# megamidi.net
KiCad netlist of a schematic drawn in EAGLE
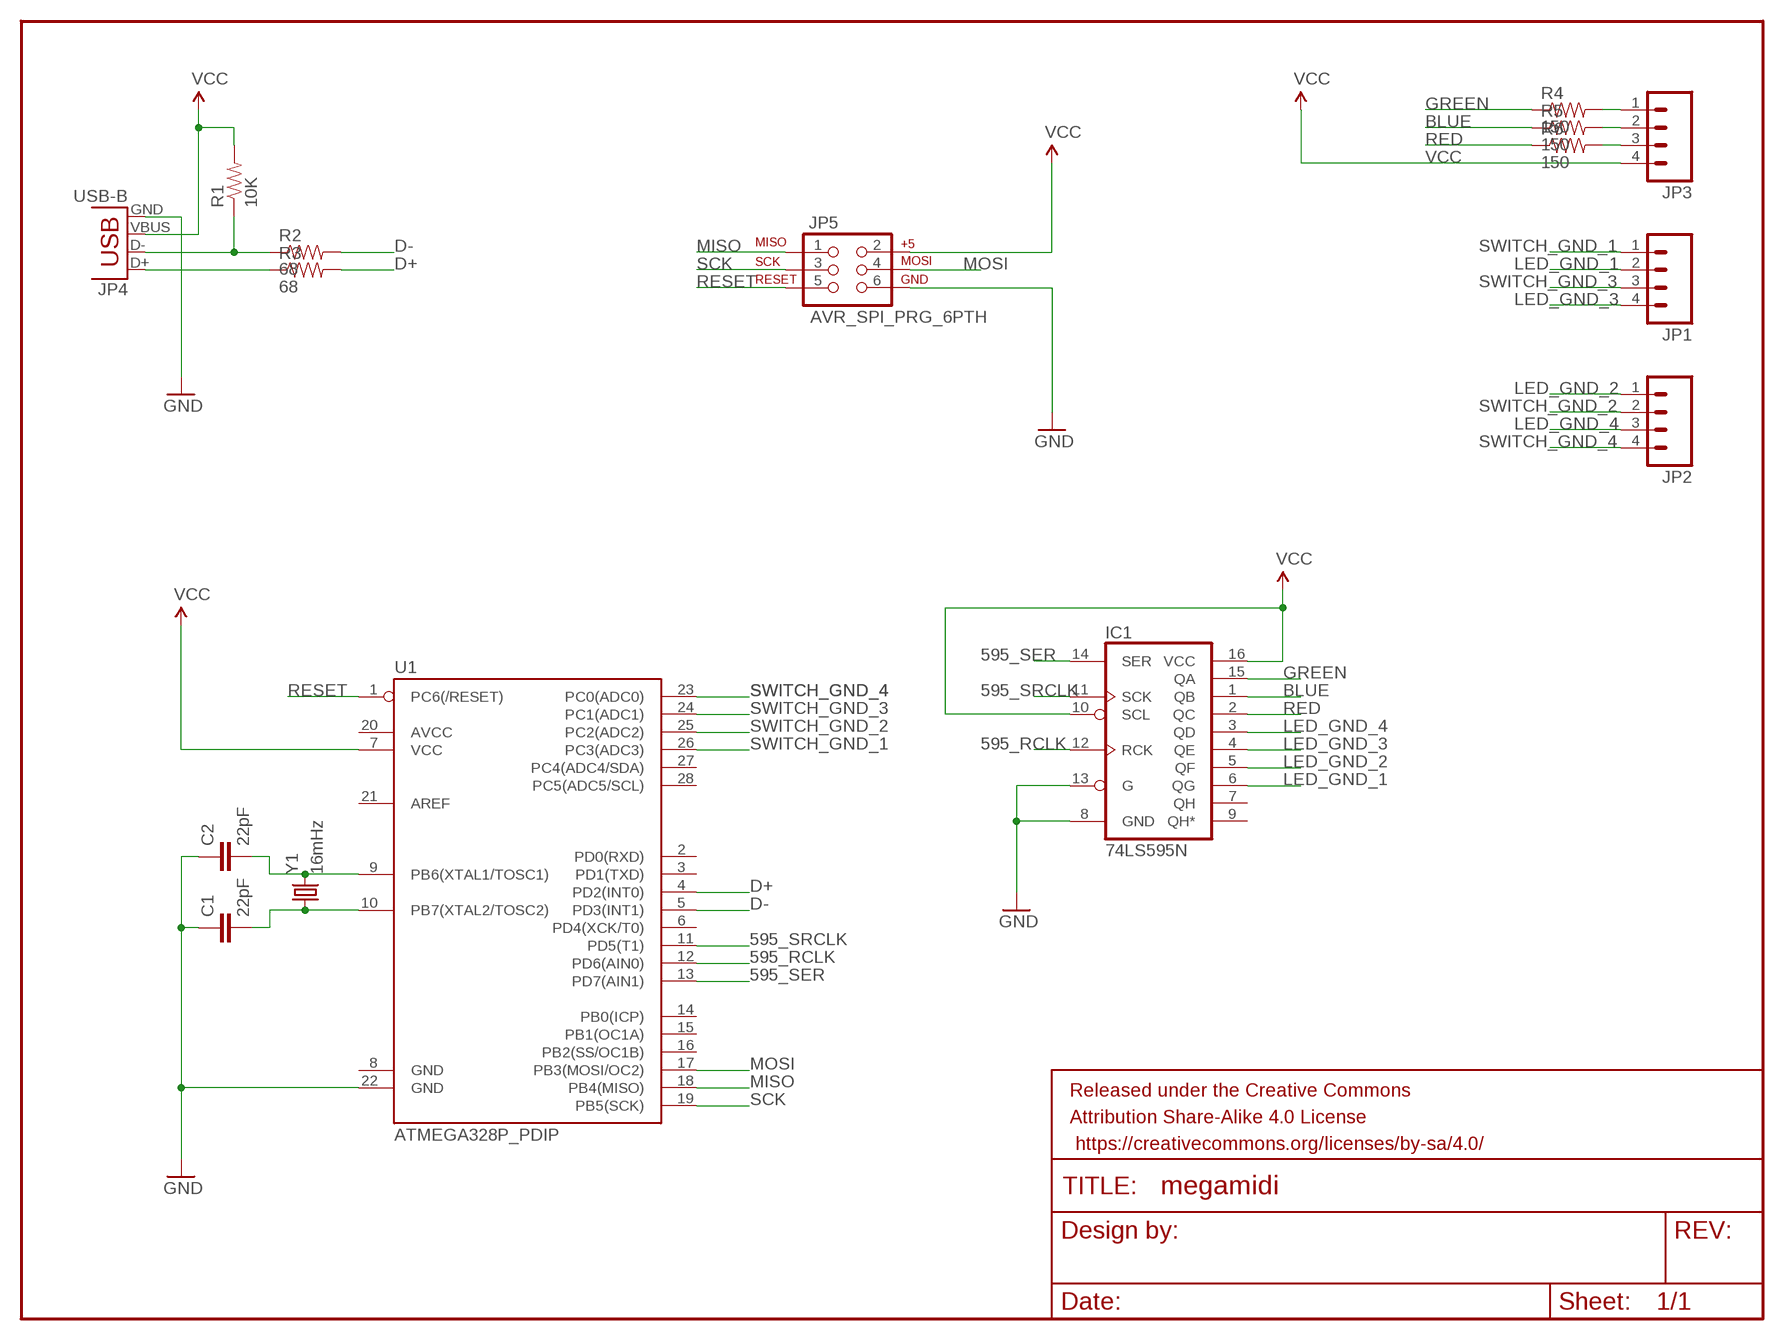
[diagram p0: schematic, sheet 1]

(export (version "E")
  (design (tool "Eeschema 10.0.6"))
  (components
    (comp (ref "C1")
      (value "22pF")
      (footprint "eagle-import:CAP-PTH-SMALL")
      (libsource (lib "eagle-import") (part "CAPPTH"))
    )
    (comp (ref "C2")
      (value "22pF")
      (footprint "eagle-import:CAP-PTH-SMALL")
      (libsource (lib "eagle-import") (part "CAPPTH"))
    )
    (comp (ref "FRAME1")
      (value "FRAME-LETTER")
      (footprint "eagle-import:CREATIVE_COMMONS")
      (libsource (lib "eagle-import") (part "FRAME-LETTER"))
    )
    (comp (ref "IC1")
      (value "74LS595N")
      (footprint "eagle-import:DIL16")
      (libsource (lib "eagle-import") (part "74595NLS"))
    )
    (comp (ref "JP1")
      (value "M04PTH")
      (footprint "eagle-import:1X04")
      (libsource (lib "eagle-import") (part "M04PTH"))
    )
    (comp (ref "JP2")
      (value "M04PTH")
      (footprint "eagle-import:1X04")
      (libsource (lib "eagle-import") (part "M04PTH"))
    )
    (comp (ref "JP3")
      (value "M04PTH")
      (footprint "eagle-import:1X04")
      (libsource (lib "eagle-import") (part "M04PTH"))
    )
    (comp (ref "JP4")
      (value "USB-B")
      (footprint "eagle-import:USB-B-PTH")
      (libsource (lib "eagle-import") (part "USBPTH"))
    )
    (comp (ref "JP5")
      (value "AVR_SPI_PRG_6PTH")
      (footprint "eagle-import:2X3")
      (libsource (lib "eagle-import") (part "AVR_SPI_PRG_6PTH"))
    )
    (comp (ref "R1")
      (value "10K")
      (footprint "eagle-import:AXIAL-0.1")
      (libsource (lib "eagle-import") (part "RESISTORPTH-1/4W-VERT"))
    )
    (comp (ref "R2")
      (value "68")
      (footprint "eagle-import:AXIAL-0.1")
      (libsource (lib "eagle-import") (part "RESISTORPTH-1/4W-VERT"))
    )
    (comp (ref "R3")
      (value "68")
      (footprint "eagle-import:AXIAL-0.1")
      (libsource (lib "eagle-import") (part "RESISTORPTH-1/4W-VERT"))
    )
    (comp (ref "R4")
      (value "150")
      (footprint "eagle-import:AXIAL-0.1")
      (libsource (lib "eagle-import") (part "RESISTORPTH-1/4W-VERT"))
    )
    (comp (ref "R5")
      (value "150")
      (footprint "eagle-import:AXIAL-0.1")
      (libsource (lib "eagle-import") (part "RESISTORPTH-1/4W-VERT"))
    )
    (comp (ref "R6")
      (value "150")
      (footprint "eagle-import:AXIAL-0.1")
      (libsource (lib "eagle-import") (part "RESISTORPTH-1/4W-VERT"))
    )
    (comp (ref "U1")
      (value "ATMEGA328P_PDIP")
      (footprint "eagle-import:DIL28-3")
      (libsource (lib "eagle-import") (part "ATMEGA328P_PDIP"))
    )
    (comp (ref "Y1")
      (value "16mHz")
      (footprint "eagle-import:HC49US")
      (libsource (lib "eagle-import") (part "CRYSTALHC49US"))
    )
  )
  (nets
    (net (code "1") (name "/595_RCLK") (class "Default")
      (node (ref "IC1") (pin "12") (pinfunction "RCK_12") (pintype "input"))
      (node (ref "U1") (pin "12") (pinfunction "PD6(AIN0)_12") (pintype "bidirectional"))
    )
    (net (code "2") (name "/595_SER") (class "Default")
      (node (ref "IC1") (pin "14") (pinfunction "SER_14") (pintype "input"))
      (node (ref "U1") (pin "13") (pinfunction "PD7(AIN1)_13") (pintype "bidirectional"))
    )
    (net (code "3") (name "/595_SRCLK") (class "Default")
      (node (ref "IC1") (pin "11") (pinfunction "SCK_11") (pintype "input"))
      (node (ref "U1") (pin "11") (pinfunction "PD5(T1)_11") (pintype "bidirectional"))
    )
    (net (code "4") (name "/BLUE") (class "Default")
      (node (ref "IC1") (pin "1") (pinfunction "QB_1") (pintype "tri_state"))
      (node (ref "R5") (pin "P$1") (pinfunction "1_P$1") (pintype "passive"))
    )
    (net (code "5") (name "/D+") (class "Default")
      (node (ref "R3") (pin "P$2") (pinfunction "2_P$2") (pintype "passive"))
      (node (ref "U1") (pin "4") (pinfunction "PD2(INT0)_4") (pintype "bidirectional"))
    )
    (net (code "6") (name "/D-") (class "Default")
      (node (ref "R2") (pin "P$2") (pinfunction "2_P$2") (pintype "passive"))
      (node (ref "U1") (pin "5") (pinfunction "PD3(INT1)_5") (pintype "bidirectional"))
    )
    (net (code "7") (name "/GREEN") (class "Default")
      (node (ref "IC1") (pin "15") (pinfunction "QA_15") (pintype "tri_state"))
      (node (ref "R4") (pin "P$1") (pinfunction "1_P$1") (pintype "passive"))
    )
    (net (code "8") (name "/LED_GND_1") (class "Default")
      (node (ref "IC1") (pin "6") (pinfunction "QG_6") (pintype "tri_state"))
      (node (ref "JP1") (pin "2") (pinfunction "2_2") (pintype "passive"))
    )
    (net (code "9") (name "/LED_GND_2") (class "Default")
      (node (ref "IC1") (pin "5") (pinfunction "QF_5") (pintype "tri_state"))
      (node (ref "JP2") (pin "1") (pinfunction "1_1") (pintype "passive"))
    )
    (net (code "10") (name "/LED_GND_3") (class "Default")
      (node (ref "IC1") (pin "4") (pinfunction "QE_4") (pintype "tri_state"))
      (node (ref "JP1") (pin "4") (pinfunction "4_4") (pintype "passive"))
    )
    (net (code "11") (name "/LED_GND_4") (class "Default")
      (node (ref "IC1") (pin "3") (pinfunction "QD_3") (pintype "tri_state"))
      (node (ref "JP2") (pin "3") (pinfunction "3_3") (pintype "passive"))
    )
    (net (code "12") (name "/MISO") (class "Default")
      (node (ref "JP5") (pin "1") (pinfunction "1_1") (pintype "passive"))
      (node (ref "U1") (pin "18") (pinfunction "PB4(MISO)_18") (pintype "bidirectional"))
    )
    (net (code "13") (name "/MOSI") (class "Default")
      (node (ref "JP5") (pin "4") (pinfunction "4_4") (pintype "passive"))
      (node (ref "U1") (pin "17") (pinfunction "PB3(MOSI/OC2)_17") (pintype "bidirectional"))
    )
    (net (code "14") (name "/RED") (class "Default")
      (node (ref "IC1") (pin "2") (pinfunction "QC_2") (pintype "tri_state"))
      (node (ref "R6") (pin "P$1") (pinfunction "1_P$1") (pintype "passive"))
    )
    (net (code "15") (name "/RESET") (class "Default")
      (node (ref "JP5") (pin "5") (pinfunction "5_5") (pintype "passive"))
      (node (ref "U1") (pin "1") (pinfunction "PC6(/RESET)_1") (pintype "bidirectional"))
    )
    (net (code "16") (name "/SCK") (class "Default")
      (node (ref "JP5") (pin "3") (pinfunction "3_3") (pintype "passive"))
      (node (ref "U1") (pin "19") (pinfunction "PB5(SCK)_19") (pintype "bidirectional"))
    )
    (net (code "17") (name "/SWITCH_GND_1") (class "Default")
      (node (ref "JP1") (pin "1") (pinfunction "1_1") (pintype "passive"))
      (node (ref "U1") (pin "26") (pinfunction "PC3(ADC3)_26") (pintype "bidirectional"))
    )
    (net (code "18") (name "/SWITCH_GND_2") (class "Default")
      (node (ref "JP2") (pin "2") (pinfunction "2_2") (pintype "passive"))
      (node (ref "U1") (pin "25") (pinfunction "PC2(ADC2)_25") (pintype "bidirectional"))
    )
    (net (code "19") (name "/SWITCH_GND_3") (class "Default")
      (node (ref "JP1") (pin "3") (pinfunction "3_3") (pintype "passive"))
      (node (ref "U1") (pin "24") (pinfunction "PC1(ADC1)_24") (pintype "bidirectional"))
    )
    (net (code "20") (name "/SWITCH_GND_4") (class "Default")
      (node (ref "JP2") (pin "4") (pinfunction "4_4") (pintype "passive"))
      (node (ref "U1") (pin "23") (pinfunction "PC0(ADC0)_23") (pintype "bidirectional"))
    )
    (net (code "21") (name "GND") (class "Default")
      (node (ref "C1") (pin "1") (pinfunction "1_1") (pintype "passive"))
      (node (ref "C2") (pin "1") (pinfunction "1_1") (pintype "passive"))
      (node (ref "IC1") (pin "13") (pinfunction "G_13") (pintype "input"))
      (node (ref "IC1") (pin "8") (pinfunction "GND_8") (pintype "power_in"))
      (node (ref "JP4") (pin "GND") (pinfunction "GND_GND") (pintype "bidirectional"))
      (node (ref "JP5") (pin "6") (pinfunction "6_6") (pintype "passive"))
      (node (ref "U1") (pin "22") (pinfunction "GND_22") (pintype "bidirectional"))
    )
    (net (code "22") (name "Net-(R1-1)") (class "Default")
      (node (ref "JP4") (pin "D-") (pinfunction "D-_D-") (pintype "bidirectional"))
      (node (ref "R1") (pin "P$1") (pinfunction "1_P$1") (pintype "passive"))
      (node (ref "R2") (pin "P$1") (pinfunction "1_P$1") (pintype "passive"))
    )
    (net (code "23") (name "Net-(R3-1)") (class "Default")
      (node (ref "JP4") (pin "D+") (pinfunction "D+_D+") (pintype "bidirectional"))
      (node (ref "R3") (pin "P$1") (pinfunction "1_P$1") (pintype "passive"))
    )
    (net (code "24") (name "Net-(R4-2)") (class "Default")
      (node (ref "JP3") (pin "1") (pinfunction "1_1") (pintype "passive"))
      (node (ref "R4") (pin "P$2") (pinfunction "2_P$2") (pintype "passive"))
    )
    (net (code "25") (name "Net-(R5-2)") (class "Default")
      (node (ref "JP3") (pin "2") (pinfunction "2_2") (pintype "passive"))
      (node (ref "R5") (pin "P$2") (pinfunction "2_P$2") (pintype "passive"))
    )
    (net (code "26") (name "Net-(R6-2)") (class "Default")
      (node (ref "JP3") (pin "3") (pinfunction "3_3") (pintype "passive"))
      (node (ref "R6") (pin "P$2") (pinfunction "2_P$2") (pintype "passive"))
    )
    (net (code "27") (name "Net-(U1-PB6(XTAL1{slash}TOSC1))") (class "Default")
      (node (ref "C2") (pin "2") (pinfunction "2_2") (pintype "passive"))
      (node (ref "U1") (pin "9") (pinfunction "PB6(XTAL1/TOSC1)_9") (pintype "bidirectional"))
      (node (ref "Y1") (pin "2") (pinfunction "2_2") (pintype "passive"))
    )
    (net (code "28") (name "Net-(U1-PB7(XTAL2{slash}TOSC2))") (class "Default")
      (node (ref "C1") (pin "2") (pinfunction "2_2") (pintype "passive"))
      (node (ref "U1") (pin "10") (pinfunction "PB7(XTAL2/TOSC2)_10") (pintype "bidirectional"))
      (node (ref "Y1") (pin "1") (pinfunction "1_1") (pintype "passive"))
    )
    (net (code "29") (name "VCC") (class "Default")
      (node (ref "IC1") (pin "10") (pinfunction "SCL_10") (pintype "input"))
      (node (ref "IC1") (pin "16") (pinfunction "VCC_16") (pintype "power_in"))
      (node (ref "JP3") (pin "4") (pinfunction "4_4") (pintype "passive"))
      (node (ref "JP4") (pin "VBUS") (pinfunction "VBUS_VBUS") (pintype "bidirectional"))
      (node (ref "JP5") (pin "2") (pinfunction "2_2") (pintype "passive"))
      (node (ref "R1") (pin "P$2") (pinfunction "2_P$2") (pintype "passive"))
      (node (ref "U1") (pin "7") (pinfunction "VCC_7") (pintype "bidirectional"))
    )
    (net (code "30") (name "unconnected-(IC1-QH*-Pad9)") (class "Default")
      (node (ref "IC1") (pin "9") (pinfunction "QH*_9") (pintype "tri_state"))
    )
    (net (code "31") (name "unconnected-(IC1-QH-Pad7)") (class "Default")
      (node (ref "IC1") (pin "7") (pinfunction "QH_7") (pintype "tri_state"))
    )
    (net (code "32") (name "unconnected-(U1-AREF-Pad21)") (class "Default")
      (node (ref "U1") (pin "21") (pinfunction "AREF_21") (pintype "bidirectional"))
    )
    (net (code "33") (name "unconnected-(U1-AVCC-Pad20)") (class "Default")
      (node (ref "U1") (pin "20") (pinfunction "AVCC_20") (pintype "bidirectional"))
    )
    (net (code "34") (name "unconnected-(U1-GND-Pad8)") (class "Default")
      (node (ref "U1") (pin "8") (pinfunction "GND_8") (pintype "bidirectional"))
    )
    (net (code "35") (name "unconnected-(U1-PB0(ICP)-Pad14)") (class "Default")
      (node (ref "U1") (pin "14") (pinfunction "PB0(ICP)_14") (pintype "bidirectional"))
    )
    (net (code "36") (name "unconnected-(U1-PB1(OC1A)-Pad15)") (class "Default")
      (node (ref "U1") (pin "15") (pinfunction "PB1(OC1A)_15") (pintype "bidirectional"))
    )
    (net (code "37") (name "unconnected-(U1-PB2(SS{slash}OC1B)-Pad16)") (class "Default")
      (node (ref "U1") (pin "16") (pinfunction "PB2(SS/OC1B)_16") (pintype "bidirectional"))
    )
    (net (code "38") (name "unconnected-(U1-PC4(ADC4{slash}SDA)-Pad27)") (class "Default")
      (node (ref "U1") (pin "27") (pinfunction "PC4(ADC4/SDA)_27") (pintype "bidirectional"))
    )
    (net (code "39") (name "unconnected-(U1-PC5(ADC5{slash}SCL)-Pad28)") (class "Default")
      (node (ref "U1") (pin "28") (pinfunction "PC5(ADC5/SCL)_28") (pintype "bidirectional"))
    )
    (net (code "40") (name "unconnected-(U1-PD0(RXD)-Pad2)") (class "Default")
      (node (ref "U1") (pin "2") (pinfunction "PD0(RXD)_2") (pintype "bidirectional"))
    )
    (net (code "41") (name "unconnected-(U1-PD1(TXD)-Pad3)") (class "Default")
      (node (ref "U1") (pin "3") (pinfunction "PD1(TXD)_3") (pintype "bidirectional"))
    )
    (net (code "42") (name "unconnected-(U1-PD4(XCK{slash}T0)-Pad6)") (class "Default")
      (node (ref "U1") (pin "6") (pinfunction "PD4(XCK/T0)_6") (pintype "bidirectional"))
    )
  )
)
